# TRX_Protection.net
KiCad netlist of a schematic drawn in Altium Designer
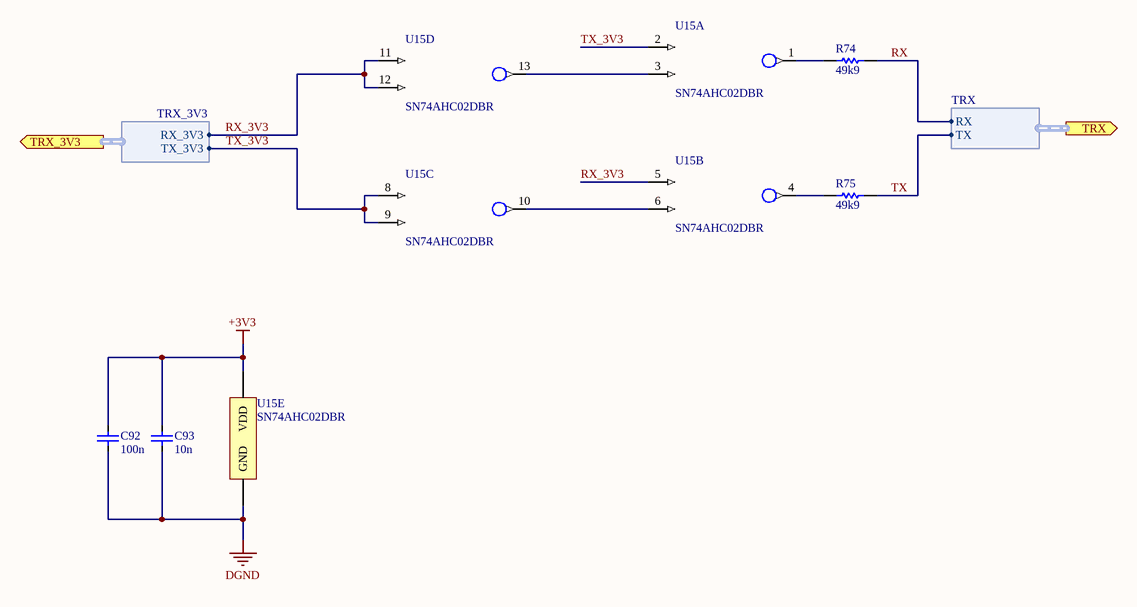
[diagram p0: TRX_Protection.SchDoc]

(export (version "E")
  (design (tool "Eeschema 10.0.6"))
  (components
    (comp (ref "C92") (value "100n") (footprint "CAP_0402") (libsource (lib "IIS-Lib_TW") (part "Cap")))
    (comp (ref "C93") (value "10n") (footprint "CAP_0402") (libsource (lib "IIS-Lib_TW") (part "Cap")))
    (comp (ref "R74") (value "49k9") (footprint "RES_0402") (libsource (lib "IIS-Lib_TW") (part "Res")))
    (comp (ref "R75") (value "49k9") (footprint "RES_0402") (libsource (lib "IIS-Lib_TW") (part "Res")))
    (comp (ref "U15")
      (value "SN74AHC02DBR")
      (footprint "SOP65P780X200-14N")
      (description "Quadruple 2-Input Positive-Nor Gates")
      (libsource (lib "IIS-Lib_TW") (part "SNx4AHC02"))
    )
  )
  (nets
    (net (code "3") (name "+3V3") (class "Default")
      (node (ref "C92") (pin "1") (pinfunction "1_1") (pintype "passive"))
      (node (ref "C93") (pin "1") (pinfunction "1_1") (pintype "passive"))
      (node (ref "U15") (pin "14") (pinfunction "VDD_14") (pintype "passive"))
    )
    (net (code "4") (name "/RX") (class "Default")
      (node (ref "R74") (pin "2") (pinfunction "2_2") (pintype "passive"))
    )
    (net (code "5") (name "/RX_3V3") (class "Default")
      (node (ref "U15") (pin "11") (pinfunction "4A_11") (pintype "input"))
      (node (ref "U15") (pin "12") (pinfunction "4B_12") (pintype "input"))
      (node (ref "U15") (pin "5") (pinfunction "2A_5") (pintype "input"))
    )
    (net (code "6") (name "/TX") (class "Default")
      (node (ref "R75") (pin "2") (pinfunction "2_2") (pintype "passive"))
    )
    (net (code "7") (name "/TX_3V3") (class "Default")
      (node (ref "U15") (pin "2") (pinfunction "1A_2") (pintype "input"))
      (node (ref "U15") (pin "8") (pinfunction "3A_8") (pintype "input"))
      (node (ref "U15") (pin "9") (pinfunction "3B_9") (pintype "input"))
    )
    (net (code "10") (name "DGND") (class "Default")
      (node (ref "C92") (pin "2") (pinfunction "2_2") (pintype "passive"))
      (node (ref "C93") (pin "2") (pinfunction "2_2") (pintype "passive"))
      (node (ref "U15") (pin "7") (pinfunction "GND_7") (pintype "passive"))
    )
    (net (code "11") (name "Net-(U15A-1B)") (class "Default")
      (node (ref "U15") (pin "13") (pinfunction "4Y_13") (pintype "output"))
      (node (ref "U15") (pin "3") (pinfunction "1B_3") (pintype "input"))
    )
    (net (code "12") (name "Net-(U15A-1Y)") (class "Default")
      (node (ref "R74") (pin "1") (pinfunction "1_1") (pintype "passive"))
      (node (ref "U15") (pin "1") (pinfunction "1Y_1") (pintype "output"))
    )
    (net (code "13") (name "Net-(U15B-2B)") (class "Default")
      (node (ref "U15") (pin "10") (pinfunction "3Y_10") (pintype "output"))
      (node (ref "U15") (pin "6") (pinfunction "2B_6") (pintype "input"))
    )
    (net (code "14") (name "Net-(U15B-2Y)") (class "Default")
      (node (ref "R75") (pin "1") (pinfunction "1_1") (pintype "passive"))
      (node (ref "U15") (pin "4") (pinfunction "2Y_4") (pintype "output"))
    )
  )
)
